# MCU.net
KiCad netlist of a schematic drawn in Altium Designer
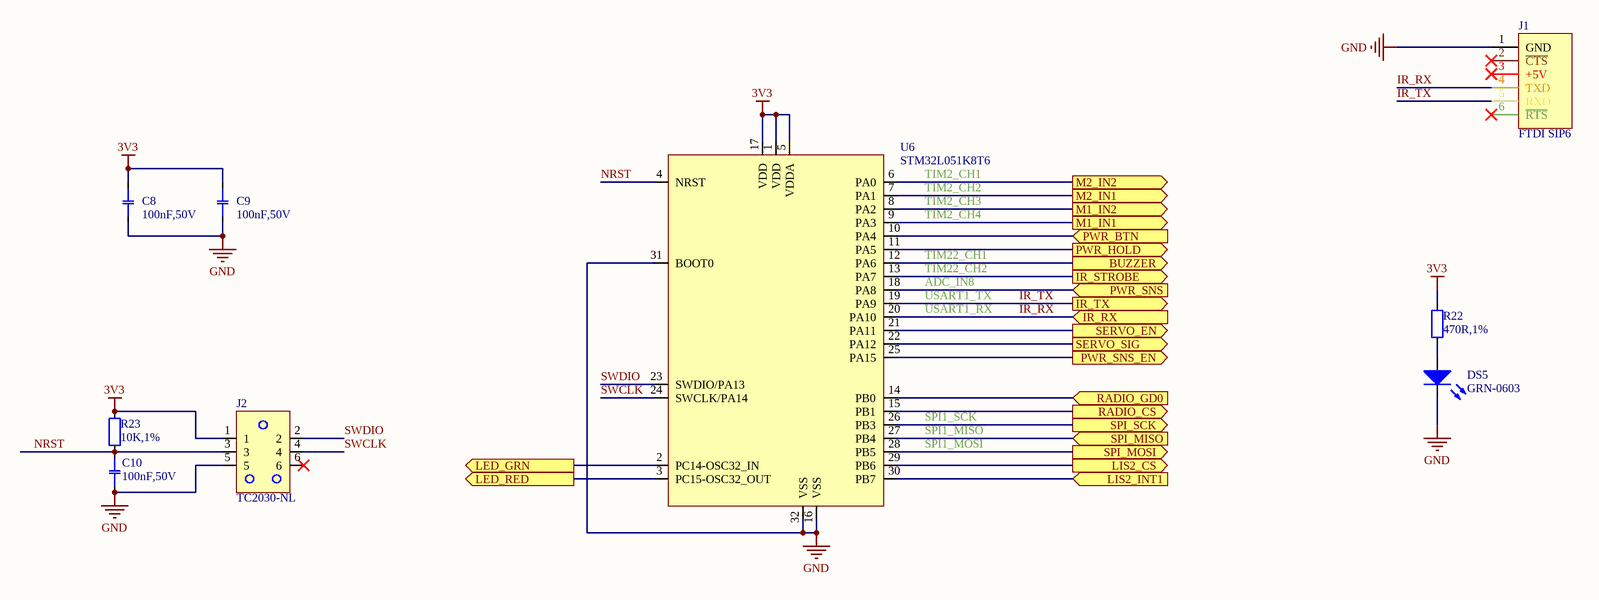
[diagram p0: MCU.SchDoc]

(export (version "E")
  (design (tool "Eeschema 10.0.6"))
  (components
    (comp (ref "C8")
      (value "100nF,50V")
      (footprint "CAPC1608X09N_0603")
      (description "CAP CER 0.1UF 50V 10% X7R 0603")
      (fields (field (name "MANUFACTURER") "Kemet") (field (name "TOLERANCE") "10%"))
      (libsource (lib "library") (part "CAP-NP_1"))
    )
    (comp (ref "C9")
      (value "100nF,50V")
      (footprint "CAPC1608X09N_0603")
      (description "CAP CER 0.1UF 50V 10% X7R 0603")
      (fields (field (name "MANUFACTURER") "Kemet") (field (name "TOLERANCE") "10%"))
      (libsource (lib "library") (part "CAP-NP_1"))
    )
    (comp (ref "C10")
      (value "100nF,50V")
      (footprint "CAPC1608X09N_0603")
      (description "CAP CER 0.1UF 50V 10% X7R 0603")
      (fields (field (name "MANUFACTURER") "Kemet") (field (name "TOLERANCE") "10%"))
      (libsource (lib "library") (part "CAP-NP_1"))
    )
    (comp (ref "DS5")
      (value "GRN-0603")
      (footprint "LED_SML-LX0603")
      (description "LED GREEN CLEAR 0603 SMD")
      (fields
        (field (name "MANUFACTURER") "Dialight")
        (field (name "MANUFACTURER PART NUMBER") "5988081107F")
      )
      (libsource (lib "library") (part "LED_1"))
    )
    (comp (ref "J1")
      (value "FTDI SIP6")
      (footprint "HIROSE_A2-6PA-2.54DSA")
      (description "FTDI Serial Header")
      (fields
        (field (name "MANUFACTURER") "Hirose Electric Co Ltd")
        (field (name "MANUFACTURER PART NUMBER") "A2-6PA-2.54DSA(71)")
      )
      (libsource (lib "library") (part "FTDI_TTL_232R"))
    )
    (comp (ref "J2")
      (value "TC2030-NL")
      (footprint "TAGCON_TC2030-IDC-NL")
      (description "Tag connect 6 way - No Legs")
      (libsource (lib "library") (part "TAGCON_TC2030-IDC"))
    )
    (comp (ref "R22")
      (value "470R,1%")
      (footprint "RESC1608X06N_0603")
      (description "RES 470 OHM 1/10W 1% 0603 SMD")
      (fields (field (name "MANUFACTURER") "Rohm Semiconductor") (field (name "POWER") "0.1W"))
      (libsource (lib "library") (part "RESISTOR_1"))
    )
    (comp (ref "R23")
      (value "10K,1%")
      (footprint "RESC1608X06N_0603")
      (description "RES 10.0K OHM 1/10W 1% 0603 SMD")
      (fields (field (name "MANUFACTURER") "Yageo") (field (name "POWER") "0.1W"))
      (libsource (lib "library") (part "RESISTOR_1"))
    )
    (comp (ref "U6")
      (value "STM32L051K8T6")
      (footprint "LQFP32")
      (description "32 Bit Mcirocontroler")
      (fields (field (name "MANUFACTURER") "ST Microelectronics"))
      (libsource (lib "library") (part "STM32L051x6/8"))
    )
  )
  (nets
    (net (code "1") (name "/BUZZER") (class "Default")
      (node (ref "U6") (pin "12") (pinfunction "PA6_12") (pintype "passive"))
    )
    (net (code "2") (name "/IR_RX") (class "Default")
      (node (ref "J1") (pin "4") (pinfunction "TXD_4") (pintype "passive"))
      (node (ref "U6") (pin "20") (pinfunction "PA10_20") (pintype "passive"))
    )
    (net (code "3") (name "/IR_STROBE") (class "Default")
      (node (ref "U6") (pin "13") (pinfunction "PA7_13") (pintype "passive"))
    )
    (net (code "4") (name "/IR_TX") (class "Default")
      (node (ref "J1") (pin "5") (pinfunction "RXD_5") (pintype "passive"))
      (node (ref "U6") (pin "19") (pinfunction "PA9_19") (pintype "passive"))
    )
    (net (code "5") (name "/LED_GRN") (class "Default")
      (node (ref "U6") (pin "2") (pinfunction "PC14-OSC32_IN_2") (pintype "passive"))
    )
    (net (code "6") (name "/LED_RED") (class "Default")
      (node (ref "U6") (pin "3") (pinfunction "PC15-OSC32_OUT_3") (pintype "passive"))
    )
    (net (code "7") (name "/LIS2_CS") (class "Default")
      (node (ref "U6") (pin "29") (pinfunction "PB6_29") (pintype "passive"))
    )
    (net (code "8") (name "/LIS2_INT1") (class "Default")
      (node (ref "U6") (pin "30") (pinfunction "PB7_30") (pintype "passive"))
    )
    (net (code "9") (name "/M1_IN1") (class "Default")
      (node (ref "U6") (pin "9") (pinfunction "PA3_9") (pintype "passive"))
    )
    (net (code "10") (name "/M1_IN2") (class "Default")
      (node (ref "U6") (pin "8") (pinfunction "PA2_8") (pintype "passive"))
    )
    (net (code "11") (name "/M2_IN1") (class "Default")
      (node (ref "U6") (pin "7") (pinfunction "PA1_7") (pintype "passive"))
    )
    (net (code "12") (name "/M2_IN2") (class "Default")
      (node (ref "U6") (pin "6") (pinfunction "PA0_6") (pintype "passive"))
    )
    (net (code "13") (name "/NRST") (class "Default")
      (node (ref "C10") (pin "1") (pinfunction "1_1") (pintype "passive"))
      (node (ref "J2") (pin "3") (pinfunction "3_3") (pintype "passive"))
      (node (ref "R23") (pin "1") (pinfunction "1_1") (pintype "passive"))
      (node (ref "U6") (pin "4") (pinfunction "NRST_4") (pintype "passive"))
    )
    (net (code "14") (name "/PWR_BTN") (class "Default")
      (node (ref "U6") (pin "10") (pinfunction "PA4_10") (pintype "passive"))
    )
    (net (code "15") (name "/PWR_HOLD") (class "Default")
      (node (ref "U6") (pin "11") (pinfunction "PA5_11") (pintype "passive"))
    )
    (net (code "16") (name "/PWR_SNS") (class "Default")
      (node (ref "U6") (pin "18") (pinfunction "PA8_18") (pintype "passive"))
    )
    (net (code "17") (name "/PWR_SNS_EN") (class "Default")
      (node (ref "U6") (pin "25") (pinfunction "PA15_25") (pintype "passive"))
    )
    (net (code "18") (name "/RADIO_CS") (class "Default")
      (node (ref "U6") (pin "15") (pinfunction "PB1_15") (pintype "passive"))
    )
    (net (code "19") (name "/RADIO_GD0") (class "Default")
      (node (ref "U6") (pin "14") (pinfunction "PB0_14") (pintype "passive"))
    )
    (net (code "20") (name "/SERVO_EN") (class "Default")
      (node (ref "U6") (pin "21") (pinfunction "PA11_21") (pintype "passive"))
    )
    (net (code "21") (name "/SERVO_SIG") (class "Default")
      (node (ref "U6") (pin "22") (pinfunction "PA12_22") (pintype "passive"))
    )
    (net (code "22") (name "/SPI_MISO") (class "Default")
      (node (ref "U6") (pin "27") (pinfunction "PB4_27") (pintype "passive"))
    )
    (net (code "23") (name "/SPI_MOSI") (class "Default")
      (node (ref "U6") (pin "28") (pinfunction "PB5_28") (pintype "passive"))
    )
    (net (code "24") (name "/SPI_SCK") (class "Default")
      (node (ref "U6") (pin "26") (pinfunction "PB3_26") (pintype "passive"))
    )
    (net (code "25") (name "/SWCLK") (class "Default")
      (node (ref "J2") (pin "4") (pinfunction "4_4") (pintype "passive"))
      (node (ref "U6") (pin "24") (pinfunction "SWCLK/PA14_24") (pintype "passive"))
    )
    (net (code "26") (name "/SWDIO") (class "Default")
      (node (ref "J2") (pin "2") (pinfunction "2_2") (pintype "passive"))
      (node (ref "U6") (pin "23") (pinfunction "SWDIO/PA13_23") (pintype "passive"))
    )
    (net (code "27") (name "3V3") (class "Default")
      (node (ref "C8") (pin "2") (pinfunction "2_2") (pintype "passive"))
      (node (ref "C9") (pin "2") (pinfunction "2_2") (pintype "passive"))
      (node (ref "J2") (pin "1") (pinfunction "1_1") (pintype "passive"))
      (node (ref "R22") (pin "2") (pinfunction "2_2") (pintype "passive"))
      (node (ref "R23") (pin "2") (pinfunction "2_2") (pintype "passive"))
      (node (ref "U6") (pin "1") (pinfunction "VDD_1") (pintype "passive"))
      (node (ref "U6") (pin "17") (pinfunction "VDD_17") (pintype "passive"))
      (node (ref "U6") (pin "5") (pinfunction "VDDA_5") (pintype "passive"))
    )
    (net (code "28") (name "GND") (class "Default")
      (node (ref "C10") (pin "2") (pinfunction "2_2") (pintype "passive"))
      (node (ref "C8") (pin "1") (pinfunction "1_1") (pintype "passive"))
      (node (ref "C9") (pin "1") (pinfunction "1_1") (pintype "passive"))
      (node (ref "DS5") (pin "1") (pinfunction "C_1") (pintype "passive"))
      (node (ref "J1") (pin "1") (pinfunction "GND_1") (pintype "passive"))
      (node (ref "J2") (pin "5") (pinfunction "5_5") (pintype "passive"))
      (node (ref "U6") (pin "16") (pinfunction "VSS_16") (pintype "passive"))
      (node (ref "U6") (pin "31") (pinfunction "BOOT0_31") (pintype "passive"))
      (node (ref "U6") (pin "32") (pinfunction "VSS_32") (pintype "passive"))
    )
    (net (code "29") (name "Net-(DS5-A)") (class "Default")
      (node (ref "DS5") (pin "2") (pinfunction "A_2") (pintype "passive"))
      (node (ref "R22") (pin "1") (pinfunction "1_1") (pintype "passive"))
    )
    (net (code "30") (name "unconnected-(J1-+5V-Pad3)") (class "Default")
      (node (ref "J1") (pin "3") (pinfunction "+5V_3") (pintype "passive+no_connect"))
    )
    (net (code "31") (name "unconnected-(J1-~{CTS}-Pad2)") (class "Default")
      (node (ref "J1") (pin "2") (pinfunction "~{CTS}_2") (pintype "passive+no_connect"))
    )
    (net (code "32") (name "unconnected-(J1-~{RTS}-Pad6)") (class "Default")
      (node (ref "J1") (pin "6") (pinfunction "~{RTS}_6") (pintype "passive+no_connect"))
    )
    (net (code "33") (name "unconnected-(J2-Pad6)") (class "Default")
      (node (ref "J2") (pin "6") (pinfunction "6_6") (pintype "passive+no_connect"))
    )
  )
)
